# RK3399_DVP_MIPI_CSI.net
KiCad netlist of a schematic drawn in Altium Designer
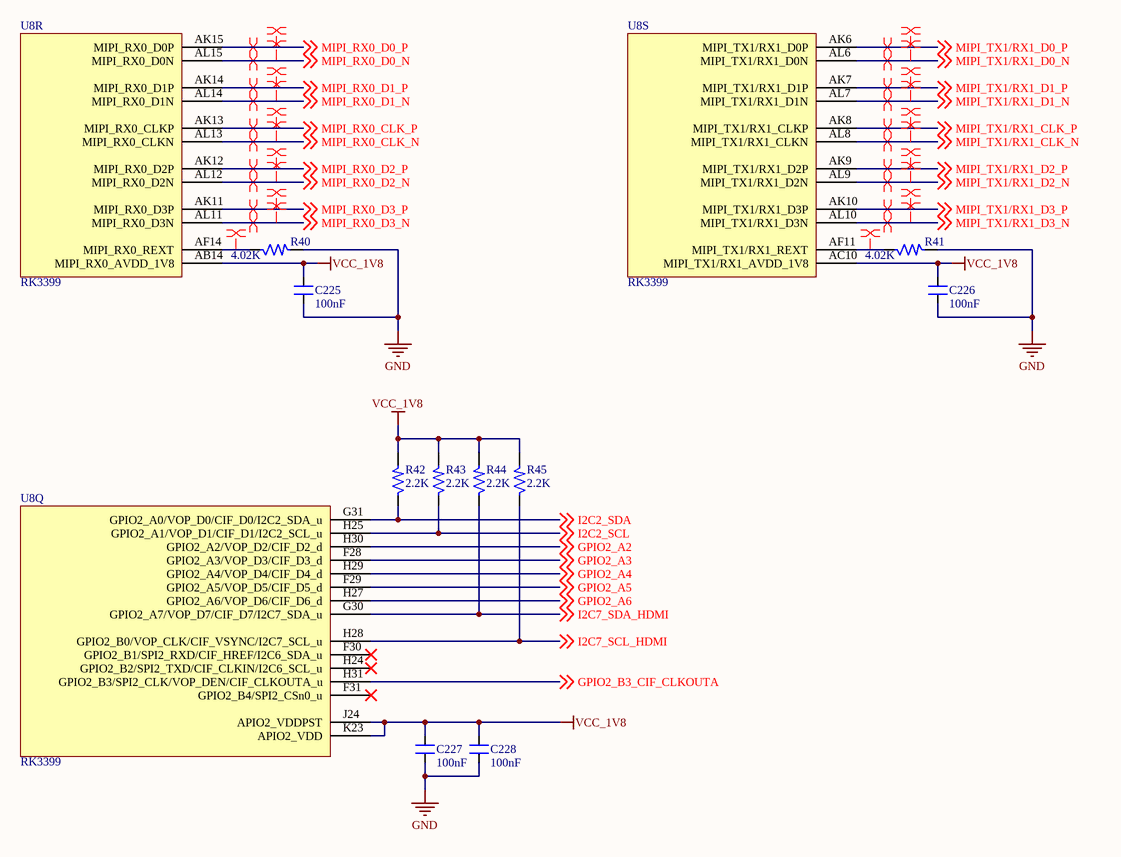
[diagram p0: RK3399_DVP_MIPI_CSI.SchDoc]

(export (version "E")
  (design (tool "Eeschema 10.0.6"))
  (components
    (comp (ref "C225")
      (value "100nF")
      (footprint "CAP_0201")
      (description "0.1µF ±10% 25V Ceramic Capacitor X5R 0201 (0603 Metric)")
      (fields
        (field (name "MANUFACTURER") "TDK Corporation")
        (field (name "MANUFACTURER PART NUMBER") "C0603X5R1E104K030BB")
      )
      (libsource (lib "EsteemPCB_SOM_Course_intlib") (part "CAP_100nF-25V-10%-0201"))
    )
    (comp (ref "C226")
      (value "100nF")
      (footprint "CAP_0201")
      (description "0.1µF ±10% 25V Ceramic Capacitor X5R 0201 (0603 Metric)")
      (fields
        (field (name "MANUFACTURER") "TDK Corporation")
        (field (name "MANUFACTURER PART NUMBER") "C0603X5R1E104K030BB")
      )
      (libsource (lib "EsteemPCB_SOM_Course_intlib") (part "CAP_100nF-25V-10%-0201"))
    )
    (comp (ref "C227")
      (value "100nF")
      (footprint "CAP_0201")
      (description "0.1µF ±10% 25V Ceramic Capacitor X5R 0201 (0603 Metric)")
      (fields
        (field (name "MANUFACTURER") "TDK Corporation")
        (field (name "MANUFACTURER PART NUMBER") "C0603X5R1E104K030BB")
      )
      (libsource (lib "EsteemPCB_SOM_Course_intlib") (part "CAP_100nF-25V-10%-0201"))
    )
    (comp (ref "C228")
      (value "100nF")
      (footprint "CAP_0201")
      (description "0.1µF ±10% 25V Ceramic Capacitor X5R 0201 (0603 Metric)")
      (fields
        (field (name "MANUFACTURER") "TDK Corporation")
        (field (name "MANUFACTURER PART NUMBER") "C0603X5R1E104K030BB")
      )
      (libsource (lib "EsteemPCB_SOM_Course_intlib") (part "CAP_100nF-25V-10%-0201"))
    )
    (comp (ref "R40")
      (value "4.02K")
      (footprint "RES_0201")
      (description "4.02 kOhms ±1% 0.05W, 1/20W Chip Resistor 0201 (0603 Metric) Thick Film")
      (fields
        (field (name "MANUFACTURER") "Yageo")
        (field (name "MANUFACTURER PART NUMBER") "RC0201FR-074K02L")
      )
      (libsource (lib "EsteemPCB_SOM_Course_intlib") (part "RES_4.02K-0.05W-1%-0201"))
    )
    (comp (ref "R41")
      (value "4.02K")
      (footprint "RES_0201")
      (description "4.02 kOhms ±1% 0.05W, 1/20W Chip Resistor 0201 (0603 Metric) Thick Film")
      (fields
        (field (name "MANUFACTURER") "Yageo")
        (field (name "MANUFACTURER PART NUMBER") "RC0201FR-074K02L")
      )
      (libsource (lib "EsteemPCB_SOM_Course_intlib") (part "RES_4.02K-0.05W-1%-0201"))
    )
    (comp (ref "R42")
      (value "2.2K")
      (footprint "RES_0201")
      (description "2.2 kOhms ±1% 0.05W, 1/20W Chip Resistor 0201 (0603 Metric) Thick Film")
      (fields
        (field (name "MANUFACTURER") "Stackpole Electronics Inc")
        (field (name "MANUFACTURER PART NUMBER") "RMCF0201FT2K20")
      )
      (libsource (lib "EsteemPCB_SOM_Course_intlib") (part "RES_2.2K-0.05W-1%-0201"))
    )
    (comp (ref "R43")
      (value "2.2K")
      (footprint "RES_0201")
      (description "2.2 kOhms ±1% 0.05W, 1/20W Chip Resistor 0201 (0603 Metric) Thick Film")
      (fields
        (field (name "MANUFACTURER") "Stackpole Electronics Inc")
        (field (name "MANUFACTURER PART NUMBER") "RMCF0201FT2K20")
      )
      (libsource (lib "EsteemPCB_SOM_Course_intlib") (part "RES_2.2K-0.05W-1%-0201"))
    )
    (comp (ref "R44")
      (value "2.2K")
      (footprint "RES_0201")
      (description "2.2 kOhms ±1% 0.05W, 1/20W Chip Resistor 0201 (0603 Metric) Thick Film")
      (fields
        (field (name "MANUFACTURER") "Stackpole Electronics Inc")
        (field (name "MANUFACTURER PART NUMBER") "RMCF0201FT2K20")
      )
      (libsource (lib "EsteemPCB_SOM_Course_intlib") (part "RES_2.2K-0.05W-1%-0201"))
    )
    (comp (ref "R45")
      (value "2.2K")
      (footprint "RES_0201")
      (description "2.2 kOhms ±1% 0.05W, 1/20W Chip Resistor 0201 (0603 Metric) Thick Film")
      (fields
        (field (name "MANUFACTURER") "Stackpole Electronics Inc")
        (field (name "MANUFACTURER PART NUMBER") "RMCF0201FT2K20")
      )
      (libsource (lib "EsteemPCB_SOM_Course_intlib") (part "RES_2.2K-0.05W-1%-0201"))
    )
    (comp (ref "U8")
      (value "RK3399")
      (footprint "FBGA828_23_826X826")
      (description "RK3399 is a low power, high performance processor for computing, personal mobile.")
      (fields (field (name "MANUFACTURER") "Rockchip"))
      (libsource (lib "EsteemPCB_SOM_Course_intlib") (part "IC_RK3399-FCBGA828"))
    )
  )
  (nets
    (net (code "1") (name "GND") (class "Default")
      (node (ref "C225") (pin "1") (pinfunction "1_1") (pintype "passive"))
      (node (ref "C226") (pin "1") (pinfunction "1_1") (pintype "passive"))
      (node (ref "C227") (pin "1") (pinfunction "1_1") (pintype "passive"))
      (node (ref "C228") (pin "1") (pinfunction "1_1") (pintype "passive"))
      (node (ref "R40") (pin "2") (pinfunction "2_2") (pintype "passive"))
      (node (ref "R41") (pin "2") (pinfunction "2_2") (pintype "passive"))
    )
    (net (code "2") (name "GPIO2_A2") (class "Default")
      (node (ref "U8") (pin "H30") (pinfunction "GPIO2_A2/VOP_D2/CIF_D2_d_H30") (pintype "passive"))
    )
    (net (code "3") (name "GPIO2_A3") (class "Default")
      (node (ref "U8") (pin "F28") (pinfunction "GPIO2_A3/VOP_D3/CIF_D3_d_F28") (pintype "passive"))
    )
    (net (code "4") (name "GPIO2_A4") (class "Default")
      (node (ref "U8") (pin "H29") (pinfunction "GPIO2_A4/VOP_D4/CIF_D4_d_H29") (pintype "passive"))
    )
    (net (code "5") (name "GPIO2_A5") (class "Default")
      (node (ref "U8") (pin "F29") (pinfunction "GPIO2_A5/VOP_D5/CIF_D5_d_F29") (pintype "passive"))
    )
    (net (code "6") (name "GPIO2_A6") (class "Default")
      (node (ref "U8") (pin "H27") (pinfunction "GPIO2_A6/VOP_D6/CIF_D6_d_H27") (pintype "passive"))
    )
    (net (code "7") (name "GPIO2_B3_CIF_CLKOUTA") (class "Default")
      (node (ref "U8") (pin "H31") (pinfunction "GPIO2_B3/SPI2_CLK/VOP_DEN/CIF_CLKOUTA_u_H31") (pintype "passive"))
    )
    (net (code "8") (name "I2C2_SCL") (class "Default")
      (node (ref "R43") (pin "1") (pinfunction "1_1") (pintype "passive"))
      (node (ref "U8") (pin "H25") (pinfunction "GPIO2_A1/VOP_D1/CIF_D1/I2C2_SCL_u_H25") (pintype "passive"))
    )
    (net (code "9") (name "I2C2_SDA") (class "Default")
      (node (ref "R42") (pin "1") (pinfunction "1_1") (pintype "passive"))
      (node (ref "U8") (pin "G31") (pinfunction "GPIO2_A0/VOP_D0/CIF_D0/I2C2_SDA_u_G31") (pintype "passive"))
    )
    (net (code "10") (name "I2C7_SCL_HDMI") (class "Default")
      (node (ref "R45") (pin "1") (pinfunction "1_1") (pintype "passive"))
      (node (ref "U8") (pin "H28") (pinfunction "GPIO2_B0/VOP_CLK/CIF_VSYNC/I2C7_SCL_u_H28") (pintype "passive"))
    )
    (net (code "11") (name "I2C7_SDA_HDMI") (class "Default")
      (node (ref "R44") (pin "1") (pinfunction "1_1") (pintype "passive"))
      (node (ref "U8") (pin "G30") (pinfunction "GPIO2_A7/VOP_D7/CIF_D7/I2C7_SDA_u_G30") (pintype "passive"))
    )
    (net (code "12") (name "MIPI_RX0_CLK_N") (class "Default")
      (node (ref "U8") (pin "AL13") (pinfunction "MIPI_RX0_CLKN_AL13") (pintype "passive"))
    )
    (net (code "13") (name "MIPI_RX0_CLK_P") (class "Default")
      (node (ref "U8") (pin "AK13") (pinfunction "MIPI_RX0_CLKP_AK13") (pintype "passive"))
    )
    (net (code "14") (name "MIPI_RX0_D0_N") (class "Default")
      (node (ref "U8") (pin "AL15") (pinfunction "MIPI_RX0_D0N_AL15") (pintype "passive"))
    )
    (net (code "15") (name "MIPI_RX0_D0_P") (class "Default")
      (node (ref "U8") (pin "AK15") (pinfunction "MIPI_RX0_D0P_AK15") (pintype "passive"))
    )
    (net (code "16") (name "MIPI_RX0_D1_N") (class "Default")
      (node (ref "U8") (pin "AL14") (pinfunction "MIPI_RX0_D1N_AL14") (pintype "passive"))
    )
    (net (code "17") (name "MIPI_RX0_D1_P") (class "Default")
      (node (ref "U8") (pin "AK14") (pinfunction "MIPI_RX0_D1P_AK14") (pintype "passive"))
    )
    (net (code "18") (name "MIPI_RX0_D2_N") (class "Default")
      (node (ref "U8") (pin "AL12") (pinfunction "MIPI_RX0_D2N_AL12") (pintype "passive"))
    )
    (net (code "19") (name "MIPI_RX0_D2_P") (class "Default")
      (node (ref "U8") (pin "AK12") (pinfunction "MIPI_RX0_D2P_AK12") (pintype "passive"))
    )
    (net (code "20") (name "MIPI_RX0_D3_N") (class "Default")
      (node (ref "U8") (pin "AL11") (pinfunction "MIPI_RX0_D3N_AL11") (pintype "passive"))
    )
    (net (code "21") (name "MIPI_RX0_D3_P") (class "Default")
      (node (ref "U8") (pin "AK11") (pinfunction "MIPI_RX0_D3P_AK11") (pintype "passive"))
    )
    (net (code "22") (name "MIPI_TX1{slash}RX1_CLK_N") (class "Default")
      (node (ref "U8") (pin "AL8") (pinfunction "MIPI_TX1/RX1_CLKN_AL8") (pintype "passive"))
    )
    (net (code "23") (name "MIPI_TX1{slash}RX1_CLK_P") (class "Default")
      (node (ref "U8") (pin "AK8") (pinfunction "MIPI_TX1/RX1_CLKP_AK8") (pintype "passive"))
    )
    (net (code "24") (name "MIPI_TX1{slash}RX1_D0_N") (class "Default")
      (node (ref "U8") (pin "AL6") (pinfunction "MIPI_TX1/RX1_D0N_AL6") (pintype "passive"))
    )
    (net (code "25") (name "MIPI_TX1{slash}RX1_D0_P") (class "Default")
      (node (ref "U8") (pin "AK6") (pinfunction "MIPI_TX1/RX1_D0P_AK6") (pintype "passive"))
    )
    (net (code "26") (name "MIPI_TX1{slash}RX1_D1_N") (class "Default")
      (node (ref "U8") (pin "AL7") (pinfunction "MIPI_TX1/RX1_D1N_AL7") (pintype "passive"))
    )
    (net (code "27") (name "MIPI_TX1{slash}RX1_D1_P") (class "Default")
      (node (ref "U8") (pin "AK7") (pinfunction "MIPI_TX1/RX1_D1P_AK7") (pintype "passive"))
    )
    (net (code "28") (name "MIPI_TX1{slash}RX1_D2_N") (class "Default")
      (node (ref "U8") (pin "AL9") (pinfunction "MIPI_TX1/RX1_D2N_AL9") (pintype "passive"))
    )
    (net (code "29") (name "MIPI_TX1{slash}RX1_D2_P") (class "Default")
      (node (ref "U8") (pin "AK9") (pinfunction "MIPI_TX1/RX1_D2P_AK9") (pintype "passive"))
    )
    (net (code "30") (name "MIPI_TX1{slash}RX1_D3_N") (class "Default")
      (node (ref "U8") (pin "AL10") (pinfunction "MIPI_TX1/RX1_D3N_AL10") (pintype "passive"))
    )
    (net (code "31") (name "MIPI_TX1{slash}RX1_D3_P") (class "Default")
      (node (ref "U8") (pin "AK10") (pinfunction "MIPI_TX1/RX1_D3P_AK10") (pintype "passive"))
    )
    (net (code "32") (name "Net-(U8R-MIPI_RX0_REXT)") (class "Default")
      (node (ref "R40") (pin "1") (pinfunction "1_1") (pintype "passive"))
      (node (ref "U8") (pin "AF14") (pinfunction "MIPI_RX0_REXT_AF14") (pintype "passive"))
    )
    (net (code "33") (name "Net-(U8S-MIPI_TX1{slash}RX1_REXT)") (class "Default")
      (node (ref "R41") (pin "1") (pinfunction "1_1") (pintype "passive"))
      (node (ref "U8") (pin "AF11") (pinfunction "MIPI_TX1/RX1_REXT_AF11") (pintype "passive"))
    )
    (net (code "34") (name "VCC_1V8") (class "Default")
      (node (ref "C225") (pin "2") (pinfunction "2_2") (pintype "passive"))
      (node (ref "C226") (pin "2") (pinfunction "2_2") (pintype "passive"))
      (node (ref "C227") (pin "2") (pinfunction "2_2") (pintype "passive"))
      (node (ref "C228") (pin "2") (pinfunction "2_2") (pintype "passive"))
      (node (ref "R42") (pin "2") (pinfunction "2_2") (pintype "passive"))
      (node (ref "R43") (pin "2") (pinfunction "2_2") (pintype "passive"))
      (node (ref "R44") (pin "2") (pinfunction "2_2") (pintype "passive"))
      (node (ref "R45") (pin "2") (pinfunction "2_2") (pintype "passive"))
      (node (ref "U8") (pin "AB14") (pinfunction "MIPI_RX0_AVDD_1V8_AB14") (pintype "passive"))
      (node (ref "U8") (pin "AC10") (pinfunction "MIPI_TX1/RX1_AVDD_1V8_AC10") (pintype "passive"))
      (node (ref "U8") (pin "J24") (pinfunction "APIO2_VDDPST_J24") (pintype "passive"))
      (node (ref "U8") (pin "K23") (pinfunction "APIO2_VDD_K23") (pintype "passive"))
    )
    (net (code "35") (name "unconnected-(U8Q-GPIO2_B1{slash}SPI2_RXD{slash}CIF_HREF{slash}I2C6_SDA_u-PadF30)") (class "Default")
      (node (ref "U8") (pin "F30") (pinfunction "GPIO2_B1/SPI2_RXD/CIF_HREF/I2C6_SDA_u_F30") (pintype "passive+no_connect"))
    )
    (net (code "36") (name "unconnected-(U8Q-GPIO2_B2{slash}SPI2_TXD{slash}CIF_CLKIN{slash}I2C6_SCL_u-PadH24)") (class "Default")
      (node (ref "U8") (pin "H24") (pinfunction "GPIO2_B2/SPI2_TXD/CIF_CLKIN/I2C6_SCL_u_H24") (pintype "passive+no_connect"))
    )
    (net (code "37") (name "unconnected-(U8Q-GPIO2_B4{slash}SPI2_CSn0_u-PadF31)") (class "Default")
      (node (ref "U8") (pin "F31") (pinfunction "GPIO2_B4/SPI2_CSn0_u_F31") (pintype "passive+no_connect"))
    )
  )
)
